# TimeSeedsVPClock.net
KiCad netlist of a schematic drawn in EAGLE
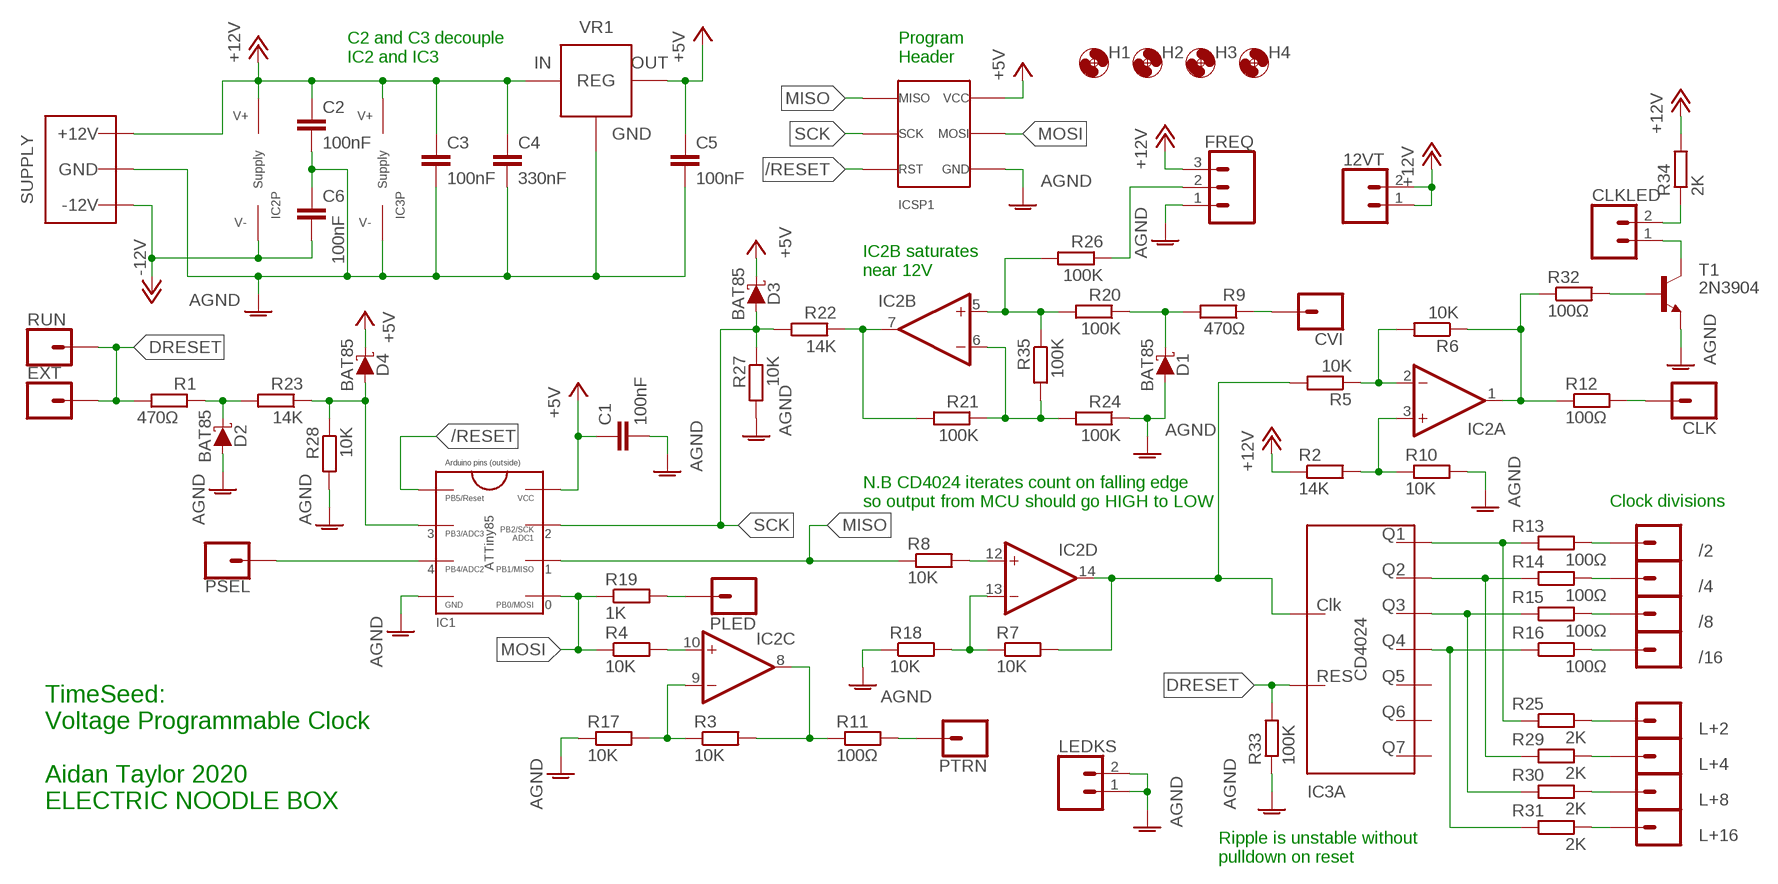
[diagram p0: schematic, sheet 1]

(export (version "E")
  (design (tool "Eeschema 10.0.6"))
  (components
    (comp (ref "/2")
      (value "1XWIREPAD")
      (footprint "eagle-import:1X01")
      (libsource (lib "eagle-import") (part "1XWIREPAD"))
    )
    (comp (ref "/4")
      (value "1XWIREPAD")
      (footprint "eagle-import:1X01")
      (libsource (lib "eagle-import") (part "1XWIREPAD"))
    )
    (comp (ref "/8")
      (value "1XWIREPAD")
      (footprint "eagle-import:1X01")
      (libsource (lib "eagle-import") (part "1XWIREPAD"))
    )
    (comp (ref "/16")
      (value "1XWIREPAD")
      (footprint "eagle-import:1X01")
      (libsource (lib "eagle-import") (part "1XWIREPAD"))
    )
    (comp (ref "12VT")
      (value "2XWIREPAD")
      (footprint "eagle-import:1X02")
      (libsource (lib "eagle-import") (part "2XWIREPAD"))
    )
    (comp (ref "C1")
      (value "100nF")
      (footprint "eagle-import:C050-025X075")
      (libsource (lib "eagle-import") (part "C-EU050-025X075"))
    )
    (comp (ref "C2")
      (value "100nF")
      (footprint "eagle-import:C050-025X075")
      (libsource (lib "eagle-import") (part "C-EU050-025X075"))
    )
    (comp (ref "C3")
      (value "100nF")
      (footprint "eagle-import:C050-025X075")
      (libsource (lib "eagle-import") (part "C-EU050-025X075"))
    )
    (comp (ref "C4")
      (value "330nF")
      (footprint "eagle-import:C050-025X075")
      (libsource (lib "eagle-import") (part "C-EU050-025X075"))
    )
    (comp (ref "C5")
      (value "100nF")
      (footprint "eagle-import:C050-025X075")
      (libsource (lib "eagle-import") (part "C-EU050-025X075"))
    )
    (comp (ref "C6")
      (value "100nF")
      (footprint "eagle-import:C050-025X075")
      (libsource (lib "eagle-import") (part "C-EU050-025X075"))
    )
    (comp (ref "CLK")
      (value "1XWIREPAD")
      (footprint "eagle-import:1X01")
      (libsource (lib "eagle-import") (part "1XWIREPAD"))
    )
    (comp (ref "CLKLED")
      (value "2XWIREPAD")
      (footprint "eagle-import:1X02")
      (libsource (lib "eagle-import") (part "2XWIREPAD"))
    )
    (comp (ref "CVI")
      (value "1XWIREPAD")
      (footprint "eagle-import:1X01")
      (libsource (lib "eagle-import") (part "1XWIREPAD"))
    )
    (comp (ref "D1")
      (value "BAT85")
      (footprint "eagle-import:DO35-7")
      (libsource (lib "eagle-import") (part "SCHOTTKY_DO35"))
    )
    (comp (ref "D2")
      (value "BAT85")
      (footprint "eagle-import:DO35-7")
      (libsource (lib "eagle-import") (part "SCHOTTKY_DO35"))
    )
    (comp (ref "D3")
      (value "BAT85")
      (footprint "eagle-import:DO35-7")
      (libsource (lib "eagle-import") (part "SCHOTTKY_DO35"))
    )
    (comp (ref "D4")
      (value "BAT85")
      (footprint "eagle-import:DO35-7")
      (libsource (lib "eagle-import") (part "SCHOTTKY_DO35"))
    )
    (comp (ref "EXT")
      (value "1XWIREPAD")
      (footprint "eagle-import:1X01")
      (libsource (lib "eagle-import") (part "1XWIREPAD"))
    )
    (comp (ref "FREQ")
      (value "3XWIREPAD")
      (footprint "eagle-import:1X03")
      (libsource (lib "eagle-import") (part "3XWIREPAD"))
    )
    (comp (ref "H1")
      (value "MOUNT-HOLE3.2")
      (footprint "eagle-import:3,2")
      (libsource (lib "eagle-import") (part "MOUNT-HOLE3.2"))
    )
    (comp (ref "H2")
      (value "MOUNT-HOLE3.2")
      (footprint "eagle-import:3,2")
      (libsource (lib "eagle-import") (part "MOUNT-HOLE3.2"))
    )
    (comp (ref "H3")
      (value "MOUNT-HOLE3.2")
      (footprint "eagle-import:3,2")
      (libsource (lib "eagle-import") (part "MOUNT-HOLE3.2"))
    )
    (comp (ref "H4")
      (value "MOUNT-HOLE3.2")
      (footprint "eagle-import:3,2")
      (libsource (lib "eagle-import") (part "MOUNT-HOLE3.2"))
    )
    (comp (ref "IC1")
      (value "ATTINY2/4/85")
      (footprint "eagle-import:DIL08")
      (libsource (lib "eagle-import") (part "ATTINY2/4/85"))
    )
    (comp (ref "IC2")
      (value "LM324")
      (footprint "eagle-import:DIL14")
      (libsource (lib "eagle-import") (part "LM324"))
    )
    (comp (ref "IC3")
      (value "CD4024BDIL")
      (footprint "eagle-import:DIL14")
      (libsource (lib "eagle-import") (part "CD4024BDIL"))
    )
    (comp (ref "ICSP1")
      (value "ICSP_2.54")
      (footprint "eagle-import:2X3")
      (libsource (lib "eagle-import") (part "ICSP_2.54"))
    )
    (comp (ref "L+2")
      (value "1XWIREPAD")
      (footprint "eagle-import:1X01")
      (libsource (lib "eagle-import") (part "1XWIREPAD"))
    )
    (comp (ref "L+4")
      (value "1XWIREPAD")
      (footprint "eagle-import:1X01")
      (libsource (lib "eagle-import") (part "1XWIREPAD"))
    )
    (comp (ref "L+8")
      (value "1XWIREPAD")
      (footprint "eagle-import:1X01")
      (libsource (lib "eagle-import") (part "1XWIREPAD"))
    )
    (comp (ref "L+16")
      (value "1XWIREPAD")
      (footprint "eagle-import:1X01")
      (libsource (lib "eagle-import") (part "1XWIREPAD"))
    )
    (comp (ref "LEDKS")
      (value "2XWIREPAD")
      (footprint "eagle-import:1X02")
      (libsource (lib "eagle-import") (part "2XWIREPAD"))
    )
    (comp (ref "PLED")
      (value "1XWIREPAD")
      (footprint "eagle-import:1X01")
      (libsource (lib "eagle-import") (part "1XWIREPAD"))
    )
    (comp (ref "PSEL")
      (value "1XWIREPAD")
      (footprint "eagle-import:1X01")
      (libsource (lib "eagle-import") (part "1XWIREPAD"))
    )
    (comp (ref "PTRN")
      (value "1XWIREPAD")
      (footprint "eagle-import:1X01")
      (libsource (lib "eagle-import") (part "1XWIREPAD"))
    )
    (comp (ref "R1")
      (value "470Ω")
      (footprint "eagle-import:0207_10")
      (libsource (lib "eagle-import") (part "R-EU_0207/10"))
    )
    (comp (ref "R2")
      (value "14K")
      (footprint "eagle-import:0207_10")
      (libsource (lib "eagle-import") (part "R-EU_0207/10"))
    )
    (comp (ref "R3")
      (value "10K")
      (footprint "eagle-import:0207_10")
      (libsource (lib "eagle-import") (part "R-EU_0207/10"))
    )
    (comp (ref "R4")
      (value "10K")
      (footprint "eagle-import:0207_10")
      (libsource (lib "eagle-import") (part "R-EU_0207/10"))
    )
    (comp (ref "R5")
      (value "10K")
      (footprint "eagle-import:0207_10")
      (libsource (lib "eagle-import") (part "R-EU_0207/10"))
    )
    (comp (ref "R6")
      (value "10K")
      (footprint "eagle-import:0207_10")
      (libsource (lib "eagle-import") (part "R-EU_0207/10"))
    )
    (comp (ref "R7")
      (value "10K")
      (footprint "eagle-import:0207_10")
      (libsource (lib "eagle-import") (part "R-EU_0207/10"))
    )
    (comp (ref "R8")
      (value "10K")
      (footprint "eagle-import:0207_10")
      (libsource (lib "eagle-import") (part "R-EU_0207/10"))
    )
    (comp (ref "R9")
      (value "470Ω")
      (footprint "eagle-import:0207_10")
      (libsource (lib "eagle-import") (part "R-EU_0207/10"))
    )
    (comp (ref "R10")
      (value "10K")
      (footprint "eagle-import:0207_10")
      (libsource (lib "eagle-import") (part "R-EU_0207/10"))
    )
    (comp (ref "R11")
      (value "100Ω")
      (footprint "eagle-import:0207_10")
      (libsource (lib "eagle-import") (part "R-EU_0207/10"))
    )
    (comp (ref "R12")
      (value "100Ω")
      (footprint "eagle-import:0207_10")
      (libsource (lib "eagle-import") (part "R-EU_0207/10"))
    )
    (comp (ref "R13")
      (value "100Ω")
      (footprint "eagle-import:0207_10")
      (libsource (lib "eagle-import") (part "R-EU_0207/10"))
    )
    (comp (ref "R14")
      (value "100Ω")
      (footprint "eagle-import:0207_10")
      (libsource (lib "eagle-import") (part "R-EU_0207/10"))
    )
    (comp (ref "R15")
      (value "100Ω")
      (footprint "eagle-import:0207_10")
      (libsource (lib "eagle-import") (part "R-EU_0207/10"))
    )
    (comp (ref "R16")
      (value "100Ω")
      (footprint "eagle-import:0207_10")
      (libsource (lib "eagle-import") (part "R-EU_0207/10"))
    )
    (comp (ref "R17")
      (value "10K")
      (footprint "eagle-import:0207_10")
      (libsource (lib "eagle-import") (part "R-EU_0207/10"))
    )
    (comp (ref "R18")
      (value "10K")
      (footprint "eagle-import:0207_10")
      (libsource (lib "eagle-import") (part "R-EU_0207/10"))
    )
    (comp (ref "R19")
      (value "1K")
      (footprint "eagle-import:0207_10")
      (libsource (lib "eagle-import") (part "R-EU_0207/10"))
    )
    (comp (ref "R20")
      (value "100K")
      (footprint "eagle-import:0207_10")
      (libsource (lib "eagle-import") (part "R-EU_0207/10"))
    )
    (comp (ref "R21")
      (value "100K")
      (footprint "eagle-import:0207_10")
      (libsource (lib "eagle-import") (part "R-EU_0207/10"))
    )
    (comp (ref "R22")
      (value "14K")
      (footprint "eagle-import:0207_10")
      (libsource (lib "eagle-import") (part "R-EU_0207/10"))
    )
    (comp (ref "R23")
      (value "14K")
      (footprint "eagle-import:0207_10")
      (libsource (lib "eagle-import") (part "R-EU_0207/10"))
    )
    (comp (ref "R24")
      (value "100K")
      (footprint "eagle-import:0207_10")
      (libsource (lib "eagle-import") (part "R-EU_0207/10"))
    )
    (comp (ref "R25")
      (value "2K")
      (footprint "eagle-import:0207_10")
      (libsource (lib "eagle-import") (part "R-EU_0207/10"))
    )
    (comp (ref "R26")
      (value "100K")
      (footprint "eagle-import:0207_10")
      (libsource (lib "eagle-import") (part "R-EU_0207/10"))
    )
    (comp (ref "R27")
      (value "10K")
      (footprint "eagle-import:0207_10")
      (libsource (lib "eagle-import") (part "R-EU_0207/10"))
    )
    (comp (ref "R28")
      (value "10K")
      (footprint "eagle-import:0207_10")
      (libsource (lib "eagle-import") (part "R-EU_0207/10"))
    )
    (comp (ref "R29")
      (value "2K")
      (footprint "eagle-import:0207_10")
      (libsource (lib "eagle-import") (part "R-EU_0207/10"))
    )
    (comp (ref "R30")
      (value "2K")
      (footprint "eagle-import:0207_10")
      (libsource (lib "eagle-import") (part "R-EU_0207/10"))
    )
    (comp (ref "R31")
      (value "2K")
      (footprint "eagle-import:0207_10")
      (libsource (lib "eagle-import") (part "R-EU_0207/10"))
    )
    (comp (ref "R32")
      (value "100Ω")
      (footprint "eagle-import:0207_10")
      (libsource (lib "eagle-import") (part "R-EU_0207/10"))
    )
    (comp (ref "R33")
      (value "100K")
      (footprint "eagle-import:0207_10")
      (libsource (lib "eagle-import") (part "R-EU_0207/10"))
    )
    (comp (ref "R34")
      (value "2K")
      (footprint "eagle-import:0207_10")
      (libsource (lib "eagle-import") (part "R-EU_0207/10"))
    )
    (comp (ref "R35")
      (value "100K")
      (footprint "eagle-import:0207_10")
      (libsource (lib "eagle-import") (part "R-EU_0207/10"))
    )
    (comp (ref "RUN")
      (value "1XWIREPAD")
      (footprint "eagle-import:1X01")
      (libsource (lib "eagle-import") (part "1XWIREPAD"))
    )
    (comp (ref "T1")
      (value "2N3904")
      (footprint "eagle-import:TO92")
      (libsource (lib "eagle-import") (part "2N3904"))
    )
    (comp (ref "VR1")
      (value "L78L05TO92")
      (footprint "eagle-import:TO92")
      (libsource (lib "eagle-import") (part "L78L05TO92"))
    )
    (comp (ref "WP1")
      (value "COMBO_SUPPLY_HEADER")
      (footprint "eagle-import:COMBINED_POWER")
      (libsource (lib "eagle-import") (part "COMBO_SUPPLY_HEADER"))
    )
  )
  (nets
    (net (code "1") (name "+5V") (class "Default")
      (node (ref "C1") (pin "1") (pinfunction "1_1") (pintype "passive"))
      (node (ref "C5") (pin "1") (pinfunction "1_1") (pintype "passive"))
      (node (ref "D3") (pin "C") (pinfunction "C_C") (pintype "passive"))
      (node (ref "D4") (pin "C") (pinfunction "C_C") (pintype "passive"))
      (node (ref "IC1") (pin "8") (pinfunction "VCC_8") (pintype "power_in"))
      (node (ref "ICSP1") (pin "2") (pinfunction "6VCC_2") (pintype "power_in"))
      (node (ref "VR1") (pin "1") (pinfunction "VOUT_1") (pintype "output"))
    )
    (net (code "2") (name "+12V") (class "Default")
      (node (ref "12VT") (pin "1") (pinfunction "1_1") (pintype "passive"))
      (node (ref "12VT") (pin "2") (pinfunction "2_2") (pintype "passive"))
      (node (ref "C2") (pin "1") (pinfunction "1_1") (pintype "passive"))
      (node (ref "C3") (pin "1") (pinfunction "1_1") (pintype "passive"))
      (node (ref "C4") (pin "1") (pinfunction "1_1") (pintype "passive"))
      (node (ref "FREQ") (pin "3") (pinfunction "3_3") (pintype "passive"))
      (node (ref "IC2") (pin "4") (pinfunction "V+_4") (pintype "bidirectional"))
      (node (ref "IC3") (pin "14") (pinfunction "V+_14") (pintype "bidirectional"))
      (node (ref "R2") (pin "1") (pinfunction "1_1") (pintype "passive"))
      (node (ref "R34") (pin "2") (pinfunction "2_2") (pintype "passive"))
      (node (ref "VR1") (pin "3") (pinfunction "VIN_3") (pintype "input"))
      (node (ref "WP1") (pin "V+1") (pinfunction "V++_V+1") (pintype "power_in"))
      (node (ref "WP1") (pin "V+2") (pinfunction "V++_V+2") (pintype "power_in"))
      (node (ref "WP1") (pin "V+3") (pinfunction "V++_V+3") (pintype "power_in"))
    )
    (net (code "3") (name "-12V") (class "Default")
      (node (ref "C6") (pin "2") (pinfunction "2_2") (pintype "passive"))
      (node (ref "IC2") (pin "11") (pinfunction "V-_11") (pintype "bidirectional"))
      (node (ref "WP1") (pin "V-1") (pinfunction "V--_V-1") (pintype "power_in"))
      (node (ref "WP1") (pin "V-2") (pinfunction "V--_V-2") (pintype "power_in"))
      (node (ref "WP1") (pin "V-3") (pinfunction "V--_V-3") (pintype "power_in"))
    )
    (net (code "4") (name "AGND") (class "Default")
      (node (ref "C1") (pin "2") (pinfunction "2_2") (pintype "passive"))
      (node (ref "C2") (pin "2") (pinfunction "2_2") (pintype "passive"))
      (node (ref "C3") (pin "2") (pinfunction "2_2") (pintype "passive"))
      (node (ref "C4") (pin "2") (pinfunction "2_2") (pintype "passive"))
      (node (ref "C5") (pin "2") (pinfunction "2_2") (pintype "passive"))
      (node (ref "C6") (pin "1") (pinfunction "1_1") (pintype "passive"))
      (node (ref "D1") (pin "A") (pinfunction "A_A") (pintype "passive"))
      (node (ref "D2") (pin "A") (pinfunction "A_A") (pintype "passive"))
      (node (ref "FREQ") (pin "1") (pinfunction "1_1") (pintype "passive"))
      (node (ref "IC1") (pin "4") (pinfunction "GND_4") (pintype "power_in"))
      (node (ref "IC3") (pin "7") (pinfunction "V-_7") (pintype "bidirectional"))
      (node (ref "ICSP1") (pin "6") (pinfunction "4GND_6") (pintype "power_in"))
      (node (ref "LEDKS") (pin "1") (pinfunction "1_1") (pintype "passive"))
      (node (ref "LEDKS") (pin "2") (pinfunction "2_2") (pintype "passive"))
      (node (ref "R10") (pin "2") (pinfunction "2_2") (pintype "passive"))
      (node (ref "R17") (pin "1") (pinfunction "1_1") (pintype "passive"))
      (node (ref "R18") (pin "1") (pinfunction "1_1") (pintype "passive"))
      (node (ref "R24") (pin "1") (pinfunction "1_1") (pintype "passive"))
      (node (ref "R27") (pin "2") (pinfunction "2_2") (pintype "passive"))
      (node (ref "R28") (pin "2") (pinfunction "2_2") (pintype "passive"))
      (node (ref "R33") (pin "1") (pinfunction "1_1") (pintype "passive"))
      (node (ref "T1") (pin "3") (pinfunction "E_3") (pintype "passive"))
      (node (ref "VR1") (pin "2") (pinfunction "GND_2") (pintype "power_in"))
      (node (ref "WP1") (pin "GND1") (pinfunction "AGND_GND1") (pintype "power_in"))
      (node (ref "WP1") (pin "GND2") (pinfunction "AGND_GND2") (pintype "power_in"))
      (node (ref "WP1") (pin "GND3") (pinfunction "AGND_GND3") (pintype "power_in"))
      (node (ref "WP1") (pin "GND4") (pinfunction "AGND_GND4") (pintype "power_in"))
      (node (ref "WP1") (pin "GND5") (pinfunction "AGND_GND5") (pintype "power_in"))
      (node (ref "WP1") (pin "GND6") (pinfunction "AGND_GND6") (pintype "power_in"))
      (node (ref "WP1") (pin "GND7") (pinfunction "AGND_GND7") (pintype "power_in"))
      (node (ref "WP1") (pin "GND8") (pinfunction "AGND_GND8") (pintype "power_in"))
    )
    (net (code "5") (name "DRESET") (class "Default")
      (node (ref "EXT") (pin "1") (pinfunction "1_1") (pintype "passive"))
      (node (ref "IC3") (pin "2") (pinfunction "RESET_2") (pintype "input"))
      (node (ref "R1") (pin "2") (pinfunction "2_2") (pintype "passive"))
      (node (ref "R33") (pin "2") (pinfunction "2_2") (pintype "passive"))
      (node (ref "RUN") (pin "1") (pinfunction "1_1") (pintype "passive"))
    )
    (net (code "6") (name "MISO") (class "Default")
      (node (ref "IC1") (pin "6") (pinfunction "PB1_6") (pintype "bidirectional"))
      (node (ref "ICSP1") (pin "1") (pinfunction "1MISO_1") (pintype "bidirectional"))
      (node (ref "R8") (pin "1") (pinfunction "1_1") (pintype "passive"))
    )
    (net (code "7") (name "MOSI") (class "Default")
      (node (ref "IC1") (pin "5") (pinfunction "PB0_5") (pintype "bidirectional"))
      (node (ref "ICSP1") (pin "4") (pinfunction "5MOSI_4") (pintype "bidirectional"))
      (node (ref "R19") (pin "1") (pinfunction "1_1") (pintype "passive"))
      (node (ref "R4") (pin "1") (pinfunction "1_1") (pintype "passive"))
    )
    (net (code "8") (name "Net-(/2-Pad1)") (class "Default")
      (node (ref "/2") (pin "1") (pinfunction "1_1") (pintype "passive"))
      (node (ref "R13") (pin "2") (pinfunction "2_2") (pintype "passive"))
    )
    (net (code "9") (name "Net-(/4-Pad1)") (class "Default")
      (node (ref "/4") (pin "1") (pinfunction "1_1") (pintype "passive"))
      (node (ref "R14") (pin "2") (pinfunction "2_2") (pintype "passive"))
    )
    (net (code "10") (name "Net-(/8-Pad1)") (class "Default")
      (node (ref "/8") (pin "1") (pinfunction "1_1") (pintype "passive"))
      (node (ref "R15") (pin "2") (pinfunction "2_2") (pintype "passive"))
    )
    (net (code "11") (name "Net-(/16-Pad1)") (class "Default")
      (node (ref "/16") (pin "1") (pinfunction "1_1") (pintype "passive"))
      (node (ref "R16") (pin "2") (pinfunction "2_2") (pintype "passive"))
    )
    (net (code "12") (name "Net-(CLK-Pad1)") (class "Default")
      (node (ref "CLK") (pin "1") (pinfunction "1_1") (pintype "passive"))
      (node (ref "R12") (pin "2") (pinfunction "2_2") (pintype "passive"))
    )
    (net (code "13") (name "Net-(CLKLED-Pad2)") (class "Default")
      (node (ref "CLKLED") (pin "2") (pinfunction "2_2") (pintype "passive"))
      (node (ref "R34") (pin "1") (pinfunction "1_1") (pintype "passive"))
    )
    (net (code "14") (name "Net-(CVI-Pad1)") (class "Default")
      (node (ref "CVI") (pin "1") (pinfunction "1_1") (pintype "passive"))
      (node (ref "R9") (pin "1") (pinfunction "1_1") (pintype "passive"))
    )
    (net (code "15") (name "Net-(D1-PadC)") (class "Default")
      (node (ref "D1") (pin "C") (pinfunction "C_C") (pintype "passive"))
      (node (ref "R20") (pin "1") (pinfunction "1_1") (pintype "passive"))
      (node (ref "R9") (pin "2") (pinfunction "2_2") (pintype "passive"))
    )
    (net (code "16") (name "Net-(D2-PadC)") (class "Default")
      (node (ref "D2") (pin "C") (pinfunction "C_C") (pintype "passive"))
      (node (ref "R1") (pin "1") (pinfunction "1_1") (pintype "passive"))
      (node (ref "R23") (pin "2") (pinfunction "2_2") (pintype "passive"))
    )
    (net (code "17") (name "Net-(FREQ-Pad2)") (class "Default")
      (node (ref "FREQ") (pin "2") (pinfunction "2_2") (pintype "passive"))
      (node (ref "R26") (pin "1") (pinfunction "1_1") (pintype "passive"))
    )
    (net (code "18") (name "Net-(IC1-PB3)") (class "Default")
      (node (ref "D4") (pin "A") (pinfunction "A_A") (pintype "passive"))
      (node (ref "IC1") (pin "2") (pinfunction "PB3_2") (pintype "bidirectional"))
      (node (ref "R23") (pin "1") (pinfunction "1_1") (pintype "passive"))
      (node (ref "R28") (pin "1") (pinfunction "1_1") (pintype "passive"))
    )
    (net (code "19") (name "Net-(IC1-PB4)") (class "Default")
      (node (ref "IC1") (pin "3") (pinfunction "PB4_3") (pintype "bidirectional"))
      (node (ref "PSEL") (pin "1") (pinfunction "1_1") (pintype "passive"))
    )
    (net (code "20") (name "Net-(IC2A-+IN)") (class "Default")
      (node (ref "IC2") (pin "3") (pinfunction "+IN_3") (pintype "input"))
      (node (ref "R10") (pin "1") (pinfunction "1_1") (pintype "passive"))
      (node (ref "R2") (pin "2") (pinfunction "2_2") (pintype "passive"))
    )
    (net (code "21") (name "Net-(IC2A--IN)") (class "Default")
      (node (ref "IC2") (pin "2") (pinfunction "-IN_2") (pintype "input"))
      (node (ref "R5") (pin "1") (pinfunction "1_1") (pintype "passive"))
      (node (ref "R6") (pin "2") (pinfunction "2_2") (pintype "passive"))
    )
    (net (code "22") (name "Net-(IC2A-OUT)") (class "Default")
      (node (ref "IC2") (pin "1") (pinfunction "OUT_1") (pintype "output"))
      (node (ref "R12") (pin "1") (pinfunction "1_1") (pintype "passive"))
      (node (ref "R32") (pin "1") (pinfunction "1_1") (pintype "passive"))
      (node (ref "R6") (pin "1") (pinfunction "1_1") (pintype "passive"))
    )
    (net (code "23") (name "Net-(IC2B-+IN)") (class "Default")
      (node (ref "IC2") (pin "5") (pinfunction "+IN_5") (pintype "input"))
      (node (ref "R20") (pin "2") (pinfunction "2_2") (pintype "passive"))
      (node (ref "R26") (pin "2") (pinfunction "2_2") (pintype "passive"))
      (node (ref "R35") (pin "1") (pinfunction "1_1") (pintype "passive"))
    )
    (net (code "24") (name "Net-(IC2B--IN)") (class "Default")
      (node (ref "IC2") (pin "6") (pinfunction "-IN_6") (pintype "input"))
      (node (ref "R21") (pin "1") (pinfunction "1_1") (pintype "passive"))
      (node (ref "R24") (pin "2") (pinfunction "2_2") (pintype "passive"))
      (node (ref "R35") (pin "2") (pinfunction "2_2") (pintype "passive"))
    )
    (net (code "25") (name "Net-(IC2B-OUT)") (class "Default")
      (node (ref "IC2") (pin "7") (pinfunction "OUT_7") (pintype "output"))
      (node (ref "R21") (pin "2") (pinfunction "2_2") (pintype "passive"))
      (node (ref "R22") (pin "1") (pinfunction "1_1") (pintype "passive"))
    )
    (net (code "26") (name "Net-(IC2C-+IN)") (class "Default")
      (node (ref "IC2") (pin "10") (pinfunction "+IN_10") (pintype "input"))
      (node (ref "R4") (pin "2") (pinfunction "2_2") (pintype "passive"))
    )
    (net (code "27") (name "Net-(IC2C--IN)") (class "Default")
      (node (ref "IC2") (pin "9") (pinfunction "-IN_9") (pintype "input"))
      (node (ref "R17") (pin "2") (pinfunction "2_2") (pintype "passive"))
      (node (ref "R3") (pin "1") (pinfunction "1_1") (pintype "passive"))
    )
    (net (code "28") (name "Net-(IC2C-OUT)") (class "Default")
      (node (ref "IC2") (pin "8") (pinfunction "OUT_8") (pintype "output"))
      (node (ref "R11") (pin "1") (pinfunction "1_1") (pintype "passive"))
      (node (ref "R3") (pin "2") (pinfunction "2_2") (pintype "passive"))
    )
    (net (code "29") (name "Net-(IC2D-+IN)") (class "Default")
      (node (ref "IC2") (pin "12") (pinfunction "+IN_12") (pintype "input"))
      (node (ref "R8") (pin "2") (pinfunction "2_2") (pintype "passive"))
    )
    (net (code "30") (name "Net-(IC2D--IN)") (class "Default")
      (node (ref "IC2") (pin "13") (pinfunction "-IN_13") (pintype "input"))
      (node (ref "R18") (pin "2") (pinfunction "2_2") (pintype "passive"))
      (node (ref "R7") (pin "1") (pinfunction "1_1") (pintype "passive"))
    )
    (net (code "31") (name "Net-(IC2D-OUT)") (class "Default")
      (node (ref "IC2") (pin "14") (pinfunction "OUT_14") (pintype "output"))
      (node (ref "IC3") (pin "1") (pinfunction "CLK_1") (pintype "input"))
      (node (ref "R5") (pin "2") (pinfunction "2_2") (pintype "passive"))
      (node (ref "R7") (pin "2") (pinfunction "2_2") (pintype "passive"))
    )
    (net (code "32") (name "Net-(IC3A-Q1)") (class "Default")
      (node (ref "IC3") (pin "12") (pinfunction "Q1_12") (pintype "output"))
      (node (ref "R13") (pin "1") (pinfunction "1_1") (pintype "passive"))
      (node (ref "R25") (pin "1") (pinfunction "1_1") (pintype "passive"))
    )
    (net (code "33") (name "Net-(IC3A-Q2)") (class "Default")
      (node (ref "IC3") (pin "11") (pinfunction "Q2_11") (pintype "output"))
      (node (ref "R14") (pin "1") (pinfunction "1_1") (pintype "passive"))
      (node (ref "R29") (pin "1") (pinfunction "1_1") (pintype "passive"))
    )
    (net (code "34") (name "Net-(IC3A-Q3)") (class "Default")
      (node (ref "IC3") (pin "9") (pinfunction "Q3_9") (pintype "output"))
      (node (ref "R15") (pin "1") (pinfunction "1_1") (pintype "passive"))
      (node (ref "R30") (pin "1") (pinfunction "1_1") (pintype "passive"))
    )
    (net (code "35") (name "Net-(IC3A-Q4)") (class "Default")
      (node (ref "IC3") (pin "6") (pinfunction "Q4_6") (pintype "output"))
      (node (ref "R16") (pin "1") (pinfunction "1_1") (pintype "passive"))
      (node (ref "R31") (pin "1") (pinfunction "1_1") (pintype "passive"))
    )
    (net (code "36") (name "Net-(L+2-Pad1)") (class "Default")
      (node (ref "L+2") (pin "1") (pinfunction "1_1") (pintype "passive"))
      (node (ref "R25") (pin "2") (pinfunction "2_2") (pintype "passive"))
    )
    (net (code "37") (name "Net-(L+4-Pad1)") (class "Default")
      (node (ref "L+4") (pin "1") (pinfunction "1_1") (pintype "passive"))
      (node (ref "R29") (pin "2") (pinfunction "2_2") (pintype "passive"))
    )
    (net (code "38") (name "Net-(L+8-Pad1)") (class "Default")
      (node (ref "L+8") (pin "1") (pinfunction "1_1") (pintype "passive"))
      (node (ref "R30") (pin "2") (pinfunction "2_2") (pintype "passive"))
    )
    (net (code "39") (name "Net-(L+16-Pad1)") (class "Default")
      (node (ref "L+16") (pin "1") (pinfunction "1_1") (pintype "passive"))
      (node (ref "R31") (pin "2") (pinfunction "2_2") (pintype "passive"))
    )
    (net (code "40") (name "Net-(PLED-Pad1)") (class "Default")
      (node (ref "PLED") (pin "1") (pinfunction "1_1") (pintype "passive"))
      (node (ref "R19") (pin "2") (pinfunction "2_2") (pintype "passive"))
    )
    (net (code "41") (name "Net-(PTRN-Pad1)") (class "Default")
      (node (ref "PTRN") (pin "1") (pinfunction "1_1") (pintype "passive"))
      (node (ref "R11") (pin "2") (pinfunction "2_2") (pintype "passive"))
    )
    (net (code "42") (name "Net-(T1-B)") (class "Default")
      (node (ref "R32") (pin "2") (pinfunction "2_2") (pintype "passive"))
      (node (ref "T1") (pin "2") (pinfunction "B_2") (pintype "passive"))
    )
    (net (code "43") (name "Net-(T1-C)") (class "Default")
      (node (ref "CLKLED") (pin "1") (pinfunction "1_1") (pintype "passive"))
      (node (ref "T1") (pin "1") (pinfunction "C_1") (pintype "passive"))
    )
    (net (code "44") (name "SCK") (class "Default")
      (node (ref "D3") (pin "A") (pinfunction "A_A") (pintype "passive"))
      (node (ref "IC1") (pin "7") (pinfunction "PB2_7") (pintype "bidirectional"))
      (node (ref "ICSP1") (pin "3") (pinfunction "2SCK_3") (pintype "bidirectional"))
      (node (ref "R22") (pin "2") (pinfunction "2_2") (pintype "passive"))
      (node (ref "R27") (pin "1") (pinfunction "1_1") (pintype "passive"))
    )
    (net (code "45") (name "unconnected-(IC3A-Q5-Pad5)") (class "Default")
      (node (ref "IC3") (pin "5") (pinfunction "Q5_5") (pintype "output"))
    )
    (net (code "46") (name "unconnected-(IC3A-Q6-Pad4)") (class "Default")
      (node (ref "IC3") (pin "4") (pinfunction "Q6_4") (pintype "output"))
    )
    (net (code "47") (name "unconnected-(IC3A-Q7-Pad3)") (class "Default")
      (node (ref "IC3") (pin "3") (pinfunction "Q7_3") (pintype "bidirectional"))
    )
    (net (code "48") (name "{slash}RESET") (class "Default")
      (node (ref "IC1") (pin "1") (pinfunction "RESET_1") (pintype "bidirectional"))
      (node (ref "ICSP1") (pin "5") (pinfunction "3RST_5") (pintype "bidirectional"))
    )
  )
)
